# PC02.net
KiCad netlist of a schematic drawn in EAGLE
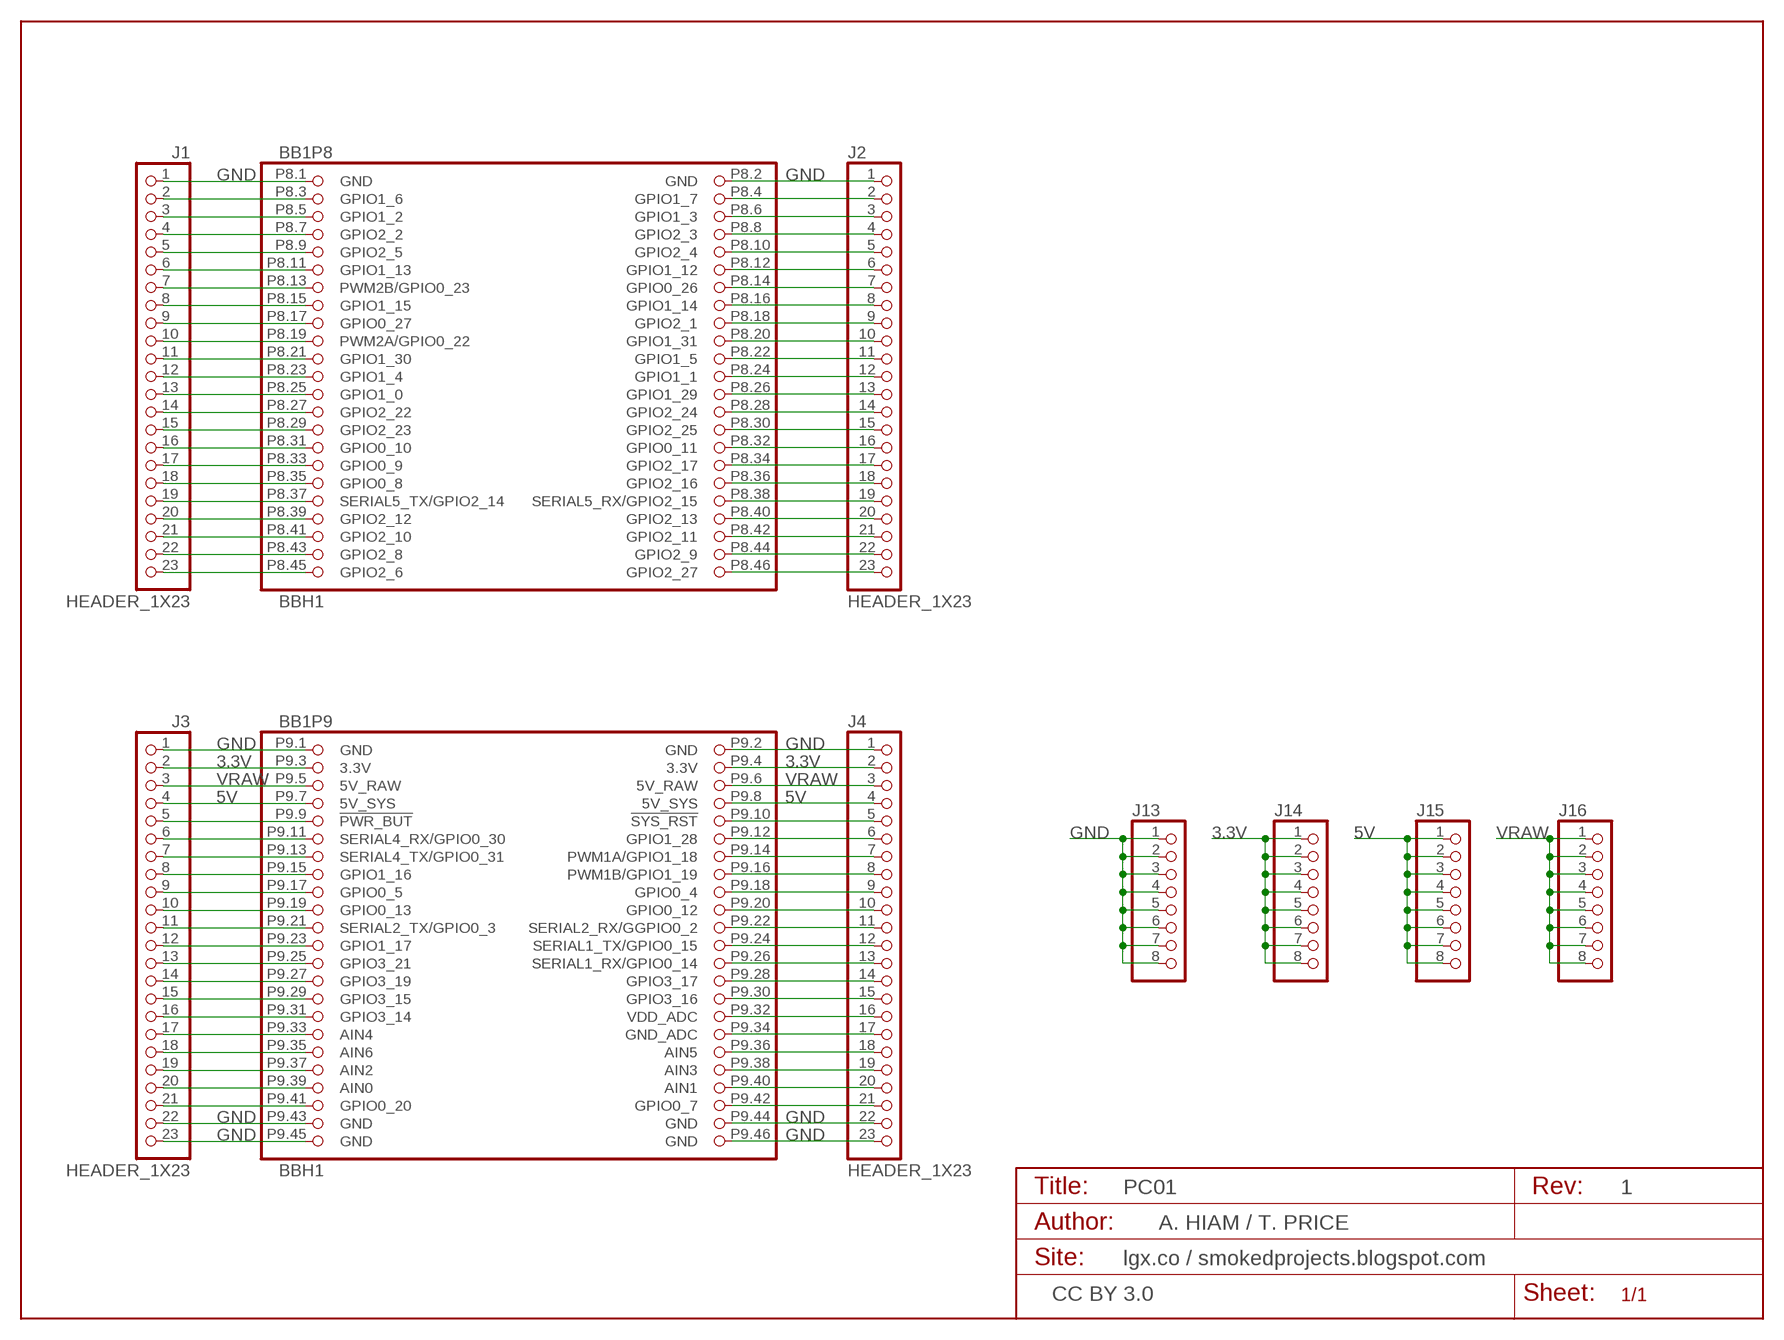
[diagram p0: schematic, sheet 1]

(export (version "E")
  (design (tool "Eeschema 10.0.6"))
  (components
    (comp (ref "BB1")
      (value "BBH1")
      (footprint "eagle-import:BB_CAPE")
      (libsource (lib "eagle-import") (part "BBH1"))
    )
    (comp (ref "J1")
      (value "HEADER_1X23")
      (footprint "eagle-import:HEADER_1X23")
      (libsource (lib "eagle-import") (part "HEADER_1X23"))
    )
    (comp (ref "J2")
      (value "HEADER_1X23")
      (footprint "eagle-import:HEADER_1X23")
      (libsource (lib "eagle-import") (part "HEADER_1X23"))
    )
    (comp (ref "J3")
      (value "HEADER_1X23")
      (footprint "eagle-import:HEADER_1X23")
      (libsource (lib "eagle-import") (part "HEADER_1X23"))
    )
    (comp (ref "J4")
      (value "HEADER_1X23")
      (footprint "eagle-import:HEADER_1X23")
      (libsource (lib "eagle-import") (part "HEADER_1X23"))
    )
    (comp (ref "J13")
      (value "HEADER_1X8")
      (footprint "eagle-import:HEADER_1X8")
      (libsource (lib "eagle-import") (part "HEADER_1X8"))
    )
    (comp (ref "J14")
      (value "HEADER_1X8")
      (footprint "eagle-import:HEADER_1X8")
      (libsource (lib "eagle-import") (part "HEADER_1X8"))
    )
    (comp (ref "J15")
      (value "HEADER_1X8")
      (footprint "eagle-import:HEADER_1X8")
      (libsource (lib "eagle-import") (part "HEADER_1X8"))
    )
    (comp (ref "J16")
      (value "HEADER_1X8")
      (footprint "eagle-import:HEADER_1X8")
      (libsource (lib "eagle-import") (part "HEADER_1X8"))
    )
  )
  (nets
    (net (code "1") (name "/3.3V") (class "Default")
      (node (ref "BB1") (pin "P9.3") (pinfunction "3.3V_P9.3") (pintype "power_in"))
      (node (ref "BB1") (pin "P9.4") (pinfunction "3.3V_P9.4") (pintype "power_in"))
      (node (ref "J14") (pin "1") (pinfunction "1_1") (pintype "passive"))
      (node (ref "J14") (pin "2") (pinfunction "2_2") (pintype "passive"))
      (node (ref "J14") (pin "3") (pinfunction "3_3") (pintype "passive"))
      (node (ref "J14") (pin "4") (pinfunction "4_4") (pintype "passive"))
      (node (ref "J14") (pin "5") (pinfunction "5_5") (pintype "passive"))
      (node (ref "J14") (pin "6") (pinfunction "6_6") (pintype "passive"))
      (node (ref "J14") (pin "7") (pinfunction "7_7") (pintype "passive"))
      (node (ref "J14") (pin "8") (pinfunction "8_8") (pintype "passive"))
      (node (ref "J3") (pin "2") (pinfunction "2_2") (pintype "passive"))
      (node (ref "J4") (pin "2") (pinfunction "2_2") (pintype "passive"))
    )
    (net (code "2") (name "/5V") (class "Default")
      (node (ref "BB1") (pin "P9.7") (pinfunction "5V_SYS_P9.7") (pintype "power_in"))
      (node (ref "BB1") (pin "P9.8") (pinfunction "5V_SYS_P9.8") (pintype "power_in"))
      (node (ref "J15") (pin "1") (pinfunction "1_1") (pintype "passive"))
      (node (ref "J15") (pin "2") (pinfunction "2_2") (pintype "passive"))
      (node (ref "J15") (pin "3") (pinfunction "3_3") (pintype "passive"))
      (node (ref "J15") (pin "4") (pinfunction "4_4") (pintype "passive"))
      (node (ref "J15") (pin "5") (pinfunction "5_5") (pintype "passive"))
      (node (ref "J15") (pin "6") (pinfunction "6_6") (pintype "passive"))
      (node (ref "J15") (pin "7") (pinfunction "7_7") (pintype "passive"))
      (node (ref "J15") (pin "8") (pinfunction "8_8") (pintype "passive"))
      (node (ref "J3") (pin "4") (pinfunction "4_4") (pintype "passive"))
      (node (ref "J4") (pin "4") (pinfunction "4_4") (pintype "passive"))
    )
    (net (code "3") (name "/GND") (class "Default")
      (node (ref "BB1") (pin "P8.1") (pinfunction "GND_P8.1") (pintype "power_in"))
      (node (ref "BB1") (pin "P8.2") (pinfunction "GND_P8.2") (pintype "power_in"))
      (node (ref "BB1") (pin "P9.1") (pinfunction "GND_P9.1") (pintype "power_in"))
      (node (ref "BB1") (pin "P9.2") (pinfunction "GND_P9.2") (pintype "power_in"))
      (node (ref "BB1") (pin "P9.43") (pinfunction "GND_P9.43") (pintype "bidirectional"))
      (node (ref "BB1") (pin "P9.44") (pinfunction "GND_P9.44") (pintype "bidirectional"))
      (node (ref "BB1") (pin "P9.45") (pinfunction "GND_P9.45") (pintype "bidirectional"))
      (node (ref "BB1") (pin "P9.46") (pinfunction "GND_P9.46") (pintype "bidirectional"))
      (node (ref "J1") (pin "1") (pinfunction "1_1") (pintype "passive"))
      (node (ref "J13") (pin "1") (pinfunction "1_1") (pintype "passive"))
      (node (ref "J13") (pin "2") (pinfunction "2_2") (pintype "passive"))
      (node (ref "J13") (pin "3") (pinfunction "3_3") (pintype "passive"))
      (node (ref "J13") (pin "4") (pinfunction "4_4") (pintype "passive"))
      (node (ref "J13") (pin "5") (pinfunction "5_5") (pintype "passive"))
      (node (ref "J13") (pin "6") (pinfunction "6_6") (pintype "passive"))
      (node (ref "J13") (pin "7") (pinfunction "7_7") (pintype "passive"))
      (node (ref "J13") (pin "8") (pinfunction "8_8") (pintype "passive"))
      (node (ref "J2") (pin "1") (pinfunction "1_1") (pintype "passive"))
      (node (ref "J3") (pin "1") (pinfunction "1_1") (pintype "passive"))
      (node (ref "J3") (pin "22") (pinfunction "22_22") (pintype "passive"))
      (node (ref "J3") (pin "23") (pinfunction "23_23") (pintype "passive"))
      (node (ref "J4") (pin "1") (pinfunction "1_1") (pintype "passive"))
      (node (ref "J4") (pin "22") (pinfunction "22_22") (pintype "passive"))
      (node (ref "J4") (pin "23") (pinfunction "23_23") (pintype "passive"))
    )
    (net (code "4") (name "/VRAW") (class "Default")
      (node (ref "BB1") (pin "P9.5") (pinfunction "5V_RAW_P9.5") (pintype "power_in"))
      (node (ref "BB1") (pin "P9.6") (pinfunction "5V_RAW_P9.6") (pintype "power_in"))
      (node (ref "J16") (pin "1") (pinfunction "1_1") (pintype "passive"))
      (node (ref "J16") (pin "2") (pinfunction "2_2") (pintype "passive"))
      (node (ref "J16") (pin "3") (pinfunction "3_3") (pintype "passive"))
      (node (ref "J16") (pin "4") (pinfunction "4_4") (pintype "passive"))
      (node (ref "J16") (pin "5") (pinfunction "5_5") (pintype "passive"))
      (node (ref "J16") (pin "6") (pinfunction "6_6") (pintype "passive"))
      (node (ref "J16") (pin "7") (pinfunction "7_7") (pintype "passive"))
      (node (ref "J16") (pin "8") (pinfunction "8_8") (pintype "passive"))
      (node (ref "J3") (pin "3") (pinfunction "3_3") (pintype "passive"))
      (node (ref "J4") (pin "3") (pinfunction "3_3") (pintype "passive"))
    )
    (net (code "5") (name "Net-(BB1A-GPIO0_8)") (class "Default")
      (node (ref "BB1") (pin "P8.35") (pinfunction "GPIO0_8_P8.35") (pintype "bidirectional"))
      (node (ref "J1") (pin "18") (pinfunction "18_18") (pintype "passive"))
    )
    (net (code "6") (name "Net-(BB1A-GPIO0_9)") (class "Default")
      (node (ref "BB1") (pin "P8.33") (pinfunction "GPIO0_9_P8.33") (pintype "bidirectional"))
      (node (ref "J1") (pin "17") (pinfunction "17_17") (pintype "passive"))
    )
    (net (code "7") (name "Net-(BB1A-GPIO0_10)") (class "Default")
      (node (ref "BB1") (pin "P8.31") (pinfunction "GPIO0_10_P8.31") (pintype "bidirectional"))
      (node (ref "J1") (pin "16") (pinfunction "16_16") (pintype "passive"))
    )
    (net (code "8") (name "Net-(BB1A-GPIO0_11)") (class "Default")
      (node (ref "BB1") (pin "P8.32") (pinfunction "GPIO0_11_P8.32") (pintype "bidirectional"))
      (node (ref "J2") (pin "16") (pinfunction "16_16") (pintype "passive"))
    )
    (net (code "9") (name "Net-(BB1A-GPIO0_26)") (class "Default")
      (node (ref "BB1") (pin "P8.14") (pinfunction "GPIO0_26_P8.14") (pintype "bidirectional"))
      (node (ref "J2") (pin "7") (pinfunction "7_7") (pintype "passive"))
    )
    (net (code "10") (name "Net-(BB1A-GPIO0_27)") (class "Default")
      (node (ref "BB1") (pin "P8.17") (pinfunction "GPIO0_27_P8.17") (pintype "bidirectional"))
      (node (ref "J1") (pin "9") (pinfunction "9_9") (pintype "passive"))
    )
    (net (code "11") (name "Net-(BB1A-GPIO1_0)") (class "Default")
      (node (ref "BB1") (pin "P8.25") (pinfunction "GPIO1_0_P8.25") (pintype "bidirectional"))
      (node (ref "J1") (pin "13") (pinfunction "13_13") (pintype "passive"))
    )
    (net (code "12") (name "Net-(BB1A-GPIO1_1)") (class "Default")
      (node (ref "BB1") (pin "P8.24") (pinfunction "GPIO1_1_P8.24") (pintype "bidirectional"))
      (node (ref "J2") (pin "12") (pinfunction "12_12") (pintype "passive"))
    )
    (net (code "13") (name "Net-(BB1A-GPIO1_2)") (class "Default")
      (node (ref "BB1") (pin "P8.5") (pinfunction "GPIO1_2_P8.5") (pintype "bidirectional"))
      (node (ref "J1") (pin "3") (pinfunction "3_3") (pintype "passive"))
    )
    (net (code "14") (name "Net-(BB1A-GPIO1_3)") (class "Default")
      (node (ref "BB1") (pin "P8.6") (pinfunction "GPIO1_3_P8.6") (pintype "bidirectional"))
      (node (ref "J2") (pin "3") (pinfunction "3_3") (pintype "passive"))
    )
    (net (code "15") (name "Net-(BB1A-GPIO1_4)") (class "Default")
      (node (ref "BB1") (pin "P8.23") (pinfunction "GPIO1_4_P8.23") (pintype "bidirectional"))
      (node (ref "J1") (pin "12") (pinfunction "12_12") (pintype "passive"))
    )
    (net (code "16") (name "Net-(BB1A-GPIO1_5)") (class "Default")
      (node (ref "BB1") (pin "P8.22") (pinfunction "GPIO1_5_P8.22") (pintype "bidirectional"))
      (node (ref "J2") (pin "11") (pinfunction "11_11") (pintype "passive"))
    )
    (net (code "17") (name "Net-(BB1A-GPIO1_6)") (class "Default")
      (node (ref "BB1") (pin "P8.3") (pinfunction "GPIO1_6_P8.3") (pintype "bidirectional"))
      (node (ref "J1") (pin "2") (pinfunction "2_2") (pintype "passive"))
    )
    (net (code "18") (name "Net-(BB1A-GPIO1_7)") (class "Default")
      (node (ref "BB1") (pin "P8.4") (pinfunction "GPIO1_7_P8.4") (pintype "bidirectional"))
      (node (ref "J2") (pin "2") (pinfunction "2_2") (pintype "passive"))
    )
    (net (code "19") (name "Net-(BB1A-GPIO1_12)") (class "Default")
      (node (ref "BB1") (pin "P8.12") (pinfunction "GPIO1_12_P8.12") (pintype "bidirectional"))
      (node (ref "J2") (pin "6") (pinfunction "6_6") (pintype "passive"))
    )
    (net (code "20") (name "Net-(BB1A-GPIO1_13)") (class "Default")
      (node (ref "BB1") (pin "P8.11") (pinfunction "GPIO1_13_P8.11") (pintype "bidirectional"))
      (node (ref "J1") (pin "6") (pinfunction "6_6") (pintype "passive"))
    )
    (net (code "21") (name "Net-(BB1A-GPIO1_14)") (class "Default")
      (node (ref "BB1") (pin "P8.16") (pinfunction "GPIO1_14_P8.16") (pintype "bidirectional"))
      (node (ref "J2") (pin "8") (pinfunction "8_8") (pintype "passive"))
    )
    (net (code "22") (name "Net-(BB1A-GPIO1_15)") (class "Default")
      (node (ref "BB1") (pin "P8.15") (pinfunction "GPIO1_15_P8.15") (pintype "bidirectional"))
      (node (ref "J1") (pin "8") (pinfunction "8_8") (pintype "passive"))
    )
    (net (code "23") (name "Net-(BB1A-GPIO1_29)") (class "Default")
      (node (ref "BB1") (pin "P8.26") (pinfunction "GPIO1_29_P8.26") (pintype "bidirectional"))
      (node (ref "J2") (pin "13") (pinfunction "13_13") (pintype "passive"))
    )
    (net (code "24") (name "Net-(BB1A-GPIO1_30)") (class "Default")
      (node (ref "BB1") (pin "P8.21") (pinfunction "GPIO1_30_P8.21") (pintype "bidirectional"))
      (node (ref "J1") (pin "11") (pinfunction "11_11") (pintype "passive"))
    )
    (net (code "25") (name "Net-(BB1A-GPIO1_31)") (class "Default")
      (node (ref "BB1") (pin "P8.20") (pinfunction "GPIO1_31_P8.20") (pintype "bidirectional"))
      (node (ref "J2") (pin "10") (pinfunction "10_10") (pintype "passive"))
    )
    (net (code "26") (name "Net-(BB1A-GPIO2_1)") (class "Default")
      (node (ref "BB1") (pin "P8.18") (pinfunction "GPIO2_1_P8.18") (pintype "bidirectional"))
      (node (ref "J2") (pin "9") (pinfunction "9_9") (pintype "passive"))
    )
    (net (code "27") (name "Net-(BB1A-GPIO2_2)") (class "Default")
      (node (ref "BB1") (pin "P8.7") (pinfunction "GPIO2_2_P8.7") (pintype "bidirectional"))
      (node (ref "J1") (pin "4") (pinfunction "4_4") (pintype "passive"))
    )
    (net (code "28") (name "Net-(BB1A-GPIO2_3)") (class "Default")
      (node (ref "BB1") (pin "P8.8") (pinfunction "GPIO2_3_P8.8") (pintype "bidirectional"))
      (node (ref "J2") (pin "4") (pinfunction "4_4") (pintype "passive"))
    )
    (net (code "29") (name "Net-(BB1A-GPIO2_4)") (class "Default")
      (node (ref "BB1") (pin "P8.10") (pinfunction "GPIO2_4_P8.10") (pintype "bidirectional"))
      (node (ref "J2") (pin "5") (pinfunction "5_5") (pintype "passive"))
    )
    (net (code "30") (name "Net-(BB1A-GPIO2_5)") (class "Default")
      (node (ref "BB1") (pin "P8.9") (pinfunction "GPIO2_5_P8.9") (pintype "bidirectional"))
      (node (ref "J1") (pin "5") (pinfunction "5_5") (pintype "passive"))
    )
    (net (code "31") (name "Net-(BB1A-GPIO2_6)") (class "Default")
      (node (ref "BB1") (pin "P8.45") (pinfunction "GPIO2_6_P8.45") (pintype "bidirectional"))
      (node (ref "J1") (pin "23") (pinfunction "23_23") (pintype "passive"))
    )
    (net (code "32") (name "Net-(BB1A-GPIO2_8)") (class "Default")
      (node (ref "BB1") (pin "P8.43") (pinfunction "GPIO2_8_P8.43") (pintype "bidirectional"))
      (node (ref "J1") (pin "22") (pinfunction "22_22") (pintype "passive"))
    )
    (net (code "33") (name "Net-(BB1A-GPIO2_9)") (class "Default")
      (node (ref "BB1") (pin "P8.44") (pinfunction "GPIO2_9_P8.44") (pintype "bidirectional"))
      (node (ref "J2") (pin "22") (pinfunction "22_22") (pintype "passive"))
    )
    (net (code "34") (name "Net-(BB1A-GPIO2_10)") (class "Default")
      (node (ref "BB1") (pin "P8.41") (pinfunction "GPIO2_10_P8.41") (pintype "bidirectional"))
      (node (ref "J1") (pin "21") (pinfunction "21_21") (pintype "passive"))
    )
    (net (code "35") (name "Net-(BB1A-GPIO2_11)") (class "Default")
      (node (ref "BB1") (pin "P8.42") (pinfunction "GPIO2_11_P8.42") (pintype "bidirectional"))
      (node (ref "J2") (pin "21") (pinfunction "21_21") (pintype "passive"))
    )
    (net (code "36") (name "Net-(BB1A-GPIO2_12)") (class "Default")
      (node (ref "BB1") (pin "P8.39") (pinfunction "GPIO2_12_P8.39") (pintype "bidirectional"))
      (node (ref "J1") (pin "20") (pinfunction "20_20") (pintype "passive"))
    )
    (net (code "37") (name "Net-(BB1A-GPIO2_13)") (class "Default")
      (node (ref "BB1") (pin "P8.40") (pinfunction "GPIO2_13_P8.40") (pintype "bidirectional"))
      (node (ref "J2") (pin "20") (pinfunction "20_20") (pintype "passive"))
    )
    (net (code "38") (name "Net-(BB1A-GPIO2_16)") (class "Default")
      (node (ref "BB1") (pin "P8.36") (pinfunction "GPIO2_16_P8.36") (pintype "bidirectional"))
      (node (ref "J2") (pin "18") (pinfunction "18_18") (pintype "passive"))
    )
    (net (code "39") (name "Net-(BB1A-GPIO2_17)") (class "Default")
      (node (ref "BB1") (pin "P8.34") (pinfunction "GPIO2_17_P8.34") (pintype "bidirectional"))
      (node (ref "J2") (pin "17") (pinfunction "17_17") (pintype "passive"))
    )
    (net (code "40") (name "Net-(BB1A-GPIO2_22)") (class "Default")
      (node (ref "BB1") (pin "P8.27") (pinfunction "GPIO2_22_P8.27") (pintype "bidirectional"))
      (node (ref "J1") (pin "14") (pinfunction "14_14") (pintype "passive"))
    )
    (net (code "41") (name "Net-(BB1A-GPIO2_23)") (class "Default")
      (node (ref "BB1") (pin "P8.29") (pinfunction "GPIO2_23_P8.29") (pintype "bidirectional"))
      (node (ref "J1") (pin "15") (pinfunction "15_15") (pintype "passive"))
    )
    (net (code "42") (name "Net-(BB1A-GPIO2_24)") (class "Default")
      (node (ref "BB1") (pin "P8.28") (pinfunction "GPIO2_24_P8.28") (pintype "bidirectional"))
      (node (ref "J2") (pin "14") (pinfunction "14_14") (pintype "passive"))
    )
    (net (code "43") (name "Net-(BB1A-GPIO2_25)") (class "Default")
      (node (ref "BB1") (pin "P8.30") (pinfunction "GPIO2_25_P8.30") (pintype "bidirectional"))
      (node (ref "J2") (pin "15") (pinfunction "15_15") (pintype "passive"))
    )
    (net (code "44") (name "Net-(BB1A-GPIO2_27)") (class "Default")
      (node (ref "BB1") (pin "P8.46") (pinfunction "GPIO2_27_P8.46") (pintype "bidirectional"))
      (node (ref "J2") (pin "23") (pinfunction "23_23") (pintype "passive"))
    )
    (net (code "45") (name "Net-(BB1A-PWM2A{slash}GPIO0_22)") (class "Default")
      (node (ref "BB1") (pin "P8.19") (pinfunction "PWM2A/GPIO0_22_P8.19") (pintype "bidirectional"))
      (node (ref "J1") (pin "10") (pinfunction "10_10") (pintype "passive"))
    )
    (net (code "46") (name "Net-(BB1A-PWM2B{slash}GPIO0_23)") (class "Default")
      (node (ref "BB1") (pin "P8.13") (pinfunction "PWM2B/GPIO0_23_P8.13") (pintype "bidirectional"))
      (node (ref "J1") (pin "7") (pinfunction "7_7") (pintype "passive"))
    )
    (net (code "47") (name "Net-(BB1A-SERIAL5_RX{slash}GPIO2_15)") (class "Default")
      (node (ref "BB1") (pin "P8.38") (pinfunction "SERIAL5_RX/GPIO2_15_P8.38") (pintype "bidirectional"))
      (node (ref "J2") (pin "19") (pinfunction "19_19") (pintype "passive"))
    )
    (net (code "48") (name "Net-(BB1A-SERIAL5_TX{slash}GPIO2_14)") (class "Default")
      (node (ref "BB1") (pin "P8.37") (pinfunction "SERIAL5_TX/GPIO2_14_P8.37") (pintype "bidirectional"))
      (node (ref "J1") (pin "19") (pinfunction "19_19") (pintype "passive"))
    )
    (net (code "49") (name "Net-(BB1B-AIN0)") (class "Default")
      (node (ref "BB1") (pin "P9.39") (pinfunction "AIN0_P9.39") (pintype "input"))
      (node (ref "J3") (pin "20") (pinfunction "20_20") (pintype "passive"))
    )
    (net (code "50") (name "Net-(BB1B-AIN1)") (class "Default")
      (node (ref "BB1") (pin "P9.40") (pinfunction "AIN1_P9.40") (pintype "input"))
      (node (ref "J4") (pin "20") (pinfunction "20_20") (pintype "passive"))
    )
    (net (code "51") (name "Net-(BB1B-AIN2)") (class "Default")
      (node (ref "BB1") (pin "P9.37") (pinfunction "AIN2_P9.37") (pintype "input"))
      (node (ref "J3") (pin "19") (pinfunction "19_19") (pintype "passive"))
    )
    (net (code "52") (name "Net-(BB1B-AIN3)") (class "Default")
      (node (ref "BB1") (pin "P9.38") (pinfunction "AIN3_P9.38") (pintype "input"))
      (node (ref "J4") (pin "19") (pinfunction "19_19") (pintype "passive"))
    )
    (net (code "53") (name "Net-(BB1B-AIN4)") (class "Default")
      (node (ref "BB1") (pin "P9.33") (pinfunction "AIN4_P9.33") (pintype "input"))
      (node (ref "J3") (pin "17") (pinfunction "17_17") (pintype "passive"))
    )
    (net (code "54") (name "Net-(BB1B-AIN5)") (class "Default")
      (node (ref "BB1") (pin "P9.36") (pinfunction "AIN5_P9.36") (pintype "input"))
      (node (ref "J4") (pin "18") (pinfunction "18_18") (pintype "passive"))
    )
    (net (code "55") (name "Net-(BB1B-AIN6)") (class "Default")
      (node (ref "BB1") (pin "P9.35") (pinfunction "AIN6_P9.35") (pintype "input"))
      (node (ref "J3") (pin "18") (pinfunction "18_18") (pintype "passive"))
    )
    (net (code "56") (name "Net-(BB1B-GND_ADC)") (class "Default")
      (node (ref "BB1") (pin "P9.34") (pinfunction "GND_ADC_P9.34") (pintype "bidirectional"))
      (node (ref "J4") (pin "17") (pinfunction "17_17") (pintype "passive"))
    )
    (net (code "57") (name "Net-(BB1B-GPIO0_4)") (class "Default")
      (node (ref "BB1") (pin "P9.18") (pinfunction "GPIO0_4_P9.18") (pintype "bidirectional"))
      (node (ref "J4") (pin "9") (pinfunction "9_9") (pintype "passive"))
    )
    (net (code "58") (name "Net-(BB1B-GPIO0_5)") (class "Default")
      (node (ref "BB1") (pin "P9.17") (pinfunction "GPIO0_5_P9.17") (pintype "bidirectional"))
      (node (ref "J3") (pin "9") (pinfunction "9_9") (pintype "passive"))
    )
    (net (code "59") (name "Net-(BB1B-GPIO0_7)") (class "Default")
      (node (ref "BB1") (pin "P9.42") (pinfunction "GPIO0_7_P9.42") (pintype "bidirectional"))
      (node (ref "J4") (pin "21") (pinfunction "21_21") (pintype "passive"))
    )
    (net (code "60") (name "Net-(BB1B-GPIO0_12)") (class "Default")
      (node (ref "BB1") (pin "P9.20") (pinfunction "GPIO0_12_P9.20") (pintype "bidirectional"))
      (node (ref "J4") (pin "10") (pinfunction "10_10") (pintype "passive"))
    )
    (net (code "61") (name "Net-(BB1B-GPIO0_13)") (class "Default")
      (node (ref "BB1") (pin "P9.19") (pinfunction "GPIO0_13_P9.19") (pintype "bidirectional"))
      (node (ref "J3") (pin "10") (pinfunction "10_10") (pintype "passive"))
    )
    (net (code "62") (name "Net-(BB1B-GPIO0_20)") (class "Default")
      (node (ref "BB1") (pin "P9.41") (pinfunction "GPIO0_20_P9.41") (pintype "bidirectional"))
      (node (ref "J3") (pin "21") (pinfunction "21_21") (pintype "passive"))
    )
    (net (code "63") (name "Net-(BB1B-GPIO1_16)") (class "Default")
      (node (ref "BB1") (pin "P9.15") (pinfunction "GPIO1_16_P9.15") (pintype "bidirectional"))
      (node (ref "J3") (pin "8") (pinfunction "8_8") (pintype "passive"))
    )
    (net (code "64") (name "Net-(BB1B-GPIO1_17)") (class "Default")
      (node (ref "BB1") (pin "P9.23") (pinfunction "GPIO1_17_P9.23") (pintype "bidirectional"))
      (node (ref "J3") (pin "12") (pinfunction "12_12") (pintype "passive"))
    )
    (net (code "65") (name "Net-(BB1B-GPIO1_28)") (class "Default")
      (node (ref "BB1") (pin "P9.12") (pinfunction "GPIO1_28_P9.12") (pintype "bidirectional"))
      (node (ref "J4") (pin "6") (pinfunction "6_6") (pintype "passive"))
    )
    (net (code "66") (name "Net-(BB1B-GPIO3_14)") (class "Default")
      (node (ref "BB1") (pin "P9.31") (pinfunction "GPIO3_14_P9.31") (pintype "bidirectional"))
      (node (ref "J3") (pin "16") (pinfunction "16_16") (pintype "passive"))
    )
    (net (code "67") (name "Net-(BB1B-GPIO3_15)") (class "Default")
      (node (ref "BB1") (pin "P9.29") (pinfunction "GPIO3_15_P9.29") (pintype "bidirectional"))
      (node (ref "J3") (pin "15") (pinfunction "15_15") (pintype "passive"))
    )
    (net (code "68") (name "Net-(BB1B-GPIO3_16)") (class "Default")
      (node (ref "BB1") (pin "P9.30") (pinfunction "GPIO3_16_P9.30") (pintype "bidirectional"))
      (node (ref "J4") (pin "15") (pinfunction "15_15") (pintype "passive"))
    )
    (net (code "69") (name "Net-(BB1B-GPIO3_17)") (class "Default")
      (node (ref "BB1") (pin "P9.28") (pinfunction "GPIO3_17_P9.28") (pintype "bidirectional"))
      (node (ref "J4") (pin "14") (pinfunction "14_14") (pintype "passive"))
    )
    (net (code "70") (name "Net-(BB1B-GPIO3_19)") (class "Default")
      (node (ref "BB1") (pin "P9.27") (pinfunction "GPIO3_19_P9.27") (pintype "bidirectional"))
      (node (ref "J3") (pin "14") (pinfunction "14_14") (pintype "passive"))
    )
    (net (code "71") (name "Net-(BB1B-GPIO3_21)") (class "Default")
      (node (ref "BB1") (pin "P9.25") (pinfunction "GPIO3_21_P9.25") (pintype "bidirectional"))
      (node (ref "J3") (pin "13") (pinfunction "13_13") (pintype "passive"))
    )
    (net (code "72") (name "Net-(BB1B-PWM1A{slash}GPIO1_18)") (class "Default")
      (node (ref "BB1") (pin "P9.14") (pinfunction "PWM1A/GPIO1_18_P9.14") (pintype "bidirectional"))
      (node (ref "J4") (pin "7") (pinfunction "7_7") (pintype "passive"))
    )
    (net (code "73") (name "Net-(BB1B-PWM1B{slash}GPIO1_19)") (class "Default")
      (node (ref "BB1") (pin "P9.16") (pinfunction "PWM1B/GPIO1_19_P9.16") (pintype "bidirectional"))
      (node (ref "J4") (pin "8") (pinfunction "8_8") (pintype "passive"))
    )
    (net (code "74") (name "Net-(BB1B-SERIAL1_RX{slash}GPIO0_14)") (class "Default")
      (node (ref "BB1") (pin "P9.26") (pinfunction "SERIAL1_RX/GPIO0_14_P9.26") (pintype "bidirectional"))
      (node (ref "J4") (pin "13") (pinfunction "13_13") (pintype "passive"))
    )
    (net (code "75") (name "Net-(BB1B-SERIAL1_TX{slash}GPIO0_15)") (class "Default")
      (node (ref "BB1") (pin "P9.24") (pinfunction "SERIAL1_TX/GPIO0_15_P9.24") (pintype "bidirectional"))
      (node (ref "J4") (pin "12") (pinfunction "12_12") (pintype "passive"))
    )
    (net (code "76") (name "Net-(BB1B-SERIAL2_RX{slash}GGPIO0_2)") (class "Default")
      (node (ref "BB1") (pin "P9.22") (pinfunction "SERIAL2_RX/GGPIO0_2_P9.22") (pintype "bidirectional"))
      (node (ref "J4") (pin "11") (pinfunction "11_11") (pintype "passive"))
    )
    (net (code "77") (name "Net-(BB1B-SERIAL2_TX{slash}GPIO0_3)") (class "Default")
      (node (ref "BB1") (pin "P9.21") (pinfunction "SERIAL2_TX/GPIO0_3_P9.21") (pintype "bidirectional"))
      (node (ref "J3") (pin "11") (pinfunction "11_11") (pintype "passive"))
    )
    (net (code "78") (name "Net-(BB1B-SERIAL4_RX{slash}GPIO0_30)") (class "Default")
      (node (ref "BB1") (pin "P9.11") (pinfunction "SERIAL4_RX/GPIO0_30_P9.11") (pintype "bidirectional"))
      (node (ref "J3") (pin "6") (pinfunction "6_6") (pintype "passive"))
    )
    (net (code "79") (name "Net-(BB1B-SERIAL4_TX{slash}GPIO0_31)") (class "Default")
      (node (ref "BB1") (pin "P9.13") (pinfunction "SERIAL4_TX/GPIO0_31_P9.13") (pintype "bidirectional"))
      (node (ref "J3") (pin "7") (pinfunction "7_7") (pintype "passive"))
    )
    (net (code "80") (name "Net-(BB1B-VDD_ADC)") (class "Default")
      (node (ref "BB1") (pin "P9.32") (pinfunction "VDD_ADC_P9.32") (pintype "bidirectional"))
      (node (ref "J4") (pin "16") (pinfunction "16_16") (pintype "passive"))
    )
    (net (code "81") (name "Net-(BB1B-~{PWR_BUT})") (class "Default")
      (node (ref "BB1") (pin "P9.9") (pinfunction "~{PWR_BUT}_P9.9") (pintype "input"))
      (node (ref "J3") (pin "5") (pinfunction "5_5") (pintype "passive"))
    )
    (net (code "82") (name "Net-(BB1B-~{SYS_RST})") (class "Default")
      (node (ref "BB1") (pin "P9.10") (pinfunction "~{SYS_RST}_P9.10") (pintype "input"))
      (node (ref "J4") (pin "5") (pinfunction "5_5") (pintype "passive"))
    )
  )
)
